# motor_controller_sch.net
KiCad netlist of a schematic drawn in EAGLE
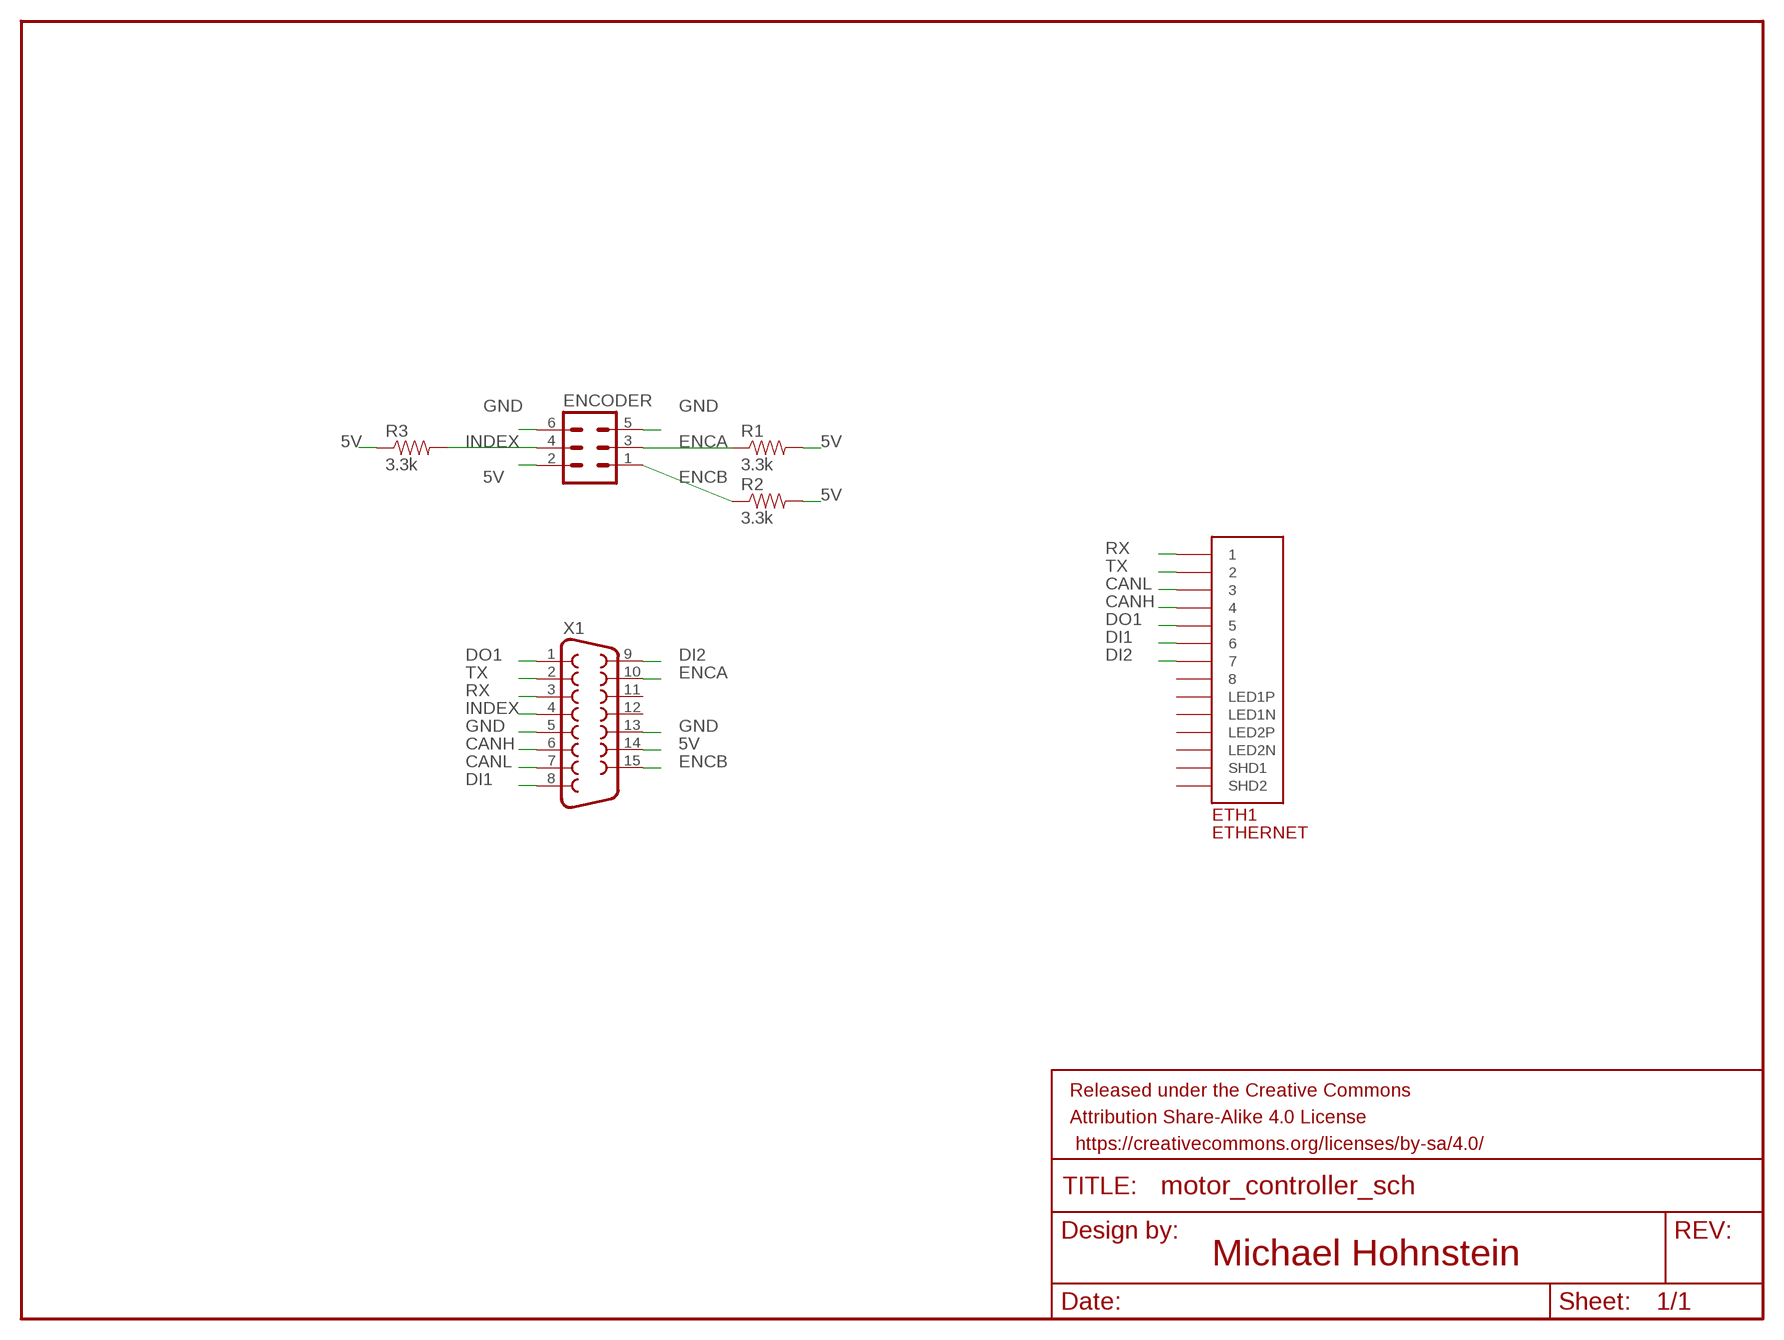
[diagram p0: schematic, sheet 1]

(export (version "E")
  (design (tool "Eeschema 10.0.6"))
  (components
    (comp (ref "ENCODER")
      (value "06V")
      (footprint "eagle-import:06V")
      (libsource (lib "eagle-import") (part "06V"))
    )
    (comp (ref "ETH1")
      (value "ETHERNET")
      (footprint "eagle-import:A122645-ND")
      (libsource (lib "eagle-import") (part "ETHERNET"))
    )
    (comp (ref "FRAME1")
      (value "FRAME-LETTER")
      (footprint "eagle-import:CREATIVE_COMMONS")
      (libsource (lib "eagle-import") (part "FRAME-LETTER"))
    )
    (comp (ref "R1")
      (value "3.3k")
      (footprint "eagle-import:0603-RES")
      (libsource (lib "eagle-import") (part "RESISTOR0603"))
    )
    (comp (ref "R2")
      (value "3.3k")
      (footprint "eagle-import:0603-RES")
      (libsource (lib "eagle-import") (part "RESISTOR0603"))
    )
    (comp (ref "R3")
      (value "3.3k")
      (footprint "eagle-import:0603-RES")
      (libsource (lib "eagle-import") (part "RESISTOR0603"))
    )
    (comp (ref "X1")
      (value "F15HP")
      (footprint "eagle-import:F15HP")
      (libsource (lib "eagle-import") (part "F15HP"))
    )
  )
  (nets
    (net (code "1") (name "/5V") (class "Default")
      (node (ref "ENCODER") (pin "2") (pinfunction "2_2") (pintype "passive"))
      (node (ref "R1") (pin "2") (pinfunction "2_2") (pintype "passive"))
      (node (ref "R2") (pin "2") (pinfunction "2_2") (pintype "passive"))
      (node (ref "R3") (pin "1") (pinfunction "1_1") (pintype "passive"))
      (node (ref "X1") (pin "14") (pinfunction "14_14") (pintype "passive"))
    )
    (net (code "2") (name "/CANH") (class "Default")
      (node (ref "ETH1") (pin "P$4") (pinfunction "4_P$4") (pintype "bidirectional"))
      (node (ref "X1") (pin "6") (pinfunction "6_6") (pintype "passive"))
    )
    (net (code "3") (name "/CANL") (class "Default")
      (node (ref "ETH1") (pin "P$3") (pinfunction "3_P$3") (pintype "bidirectional"))
      (node (ref "X1") (pin "7") (pinfunction "7_7") (pintype "passive"))
    )
    (net (code "4") (name "/DI1") (class "Default")
      (node (ref "ETH1") (pin "P$6") (pinfunction "6_P$6") (pintype "bidirectional"))
      (node (ref "X1") (pin "8") (pinfunction "8_8") (pintype "passive"))
    )
    (net (code "5") (name "/DI2") (class "Default")
      (node (ref "ETH1") (pin "P$7") (pinfunction "7_P$7") (pintype "bidirectional"))
      (node (ref "X1") (pin "9") (pinfunction "9_9") (pintype "passive"))
    )
    (net (code "6") (name "/DO1") (class "Default")
      (node (ref "ETH1") (pin "P$5") (pinfunction "5_P$5") (pintype "bidirectional"))
      (node (ref "X1") (pin "1") (pinfunction "1_1") (pintype "passive"))
    )
    (net (code "7") (name "/ENCA") (class "Default")
      (node (ref "ENCODER") (pin "3") (pinfunction "3_3") (pintype "passive"))
      (node (ref "R1") (pin "1") (pinfunction "1_1") (pintype "passive"))
      (node (ref "X1") (pin "10") (pinfunction "10_10") (pintype "passive"))
    )
    (net (code "8") (name "/ENCB") (class "Default")
      (node (ref "ENCODER") (pin "1") (pinfunction "1_1") (pintype "passive"))
      (node (ref "R2") (pin "1") (pinfunction "1_1") (pintype "passive"))
      (node (ref "X1") (pin "15") (pinfunction "15_15") (pintype "passive"))
    )
    (net (code "9") (name "/GND") (class "Default")
      (node (ref "ENCODER") (pin "5") (pinfunction "5_5") (pintype "passive"))
      (node (ref "ENCODER") (pin "6") (pinfunction "6_6") (pintype "passive"))
      (node (ref "X1") (pin "13") (pinfunction "13_13") (pintype "passive"))
      (node (ref "X1") (pin "5") (pinfunction "5_5") (pintype "passive"))
    )
    (net (code "10") (name "/INDEX") (class "Default")
      (node (ref "ENCODER") (pin "4") (pinfunction "4_4") (pintype "passive"))
      (node (ref "R3") (pin "2") (pinfunction "2_2") (pintype "passive"))
      (node (ref "X1") (pin "4") (pinfunction "4_4") (pintype "passive"))
    )
    (net (code "11") (name "/RX") (class "Default")
      (node (ref "ETH1") (pin "P$1") (pinfunction "1_P$1") (pintype "bidirectional"))
      (node (ref "X1") (pin "3") (pinfunction "3_3") (pintype "passive"))
    )
    (net (code "12") (name "/TX") (class "Default")
      (node (ref "ETH1") (pin "P$2") (pinfunction "2_P$2") (pintype "bidirectional"))
      (node (ref "X1") (pin "2") (pinfunction "2_2") (pintype "passive"))
    )
    (net (code "13") (name "unconnected-(ETH1-8-PadP$8)") (class "Default")
      (node (ref "ETH1") (pin "P$8") (pinfunction "8_P$8") (pintype "bidirectional"))
    )
    (net (code "14") (name "unconnected-(ETH1-LED1N-PadP$9)") (class "Default")
      (node (ref "ETH1") (pin "P$9") (pinfunction "LED1N_P$9") (pintype "bidirectional"))
    )
    (net (code "15") (name "unconnected-(ETH1-LED1P-PadP$10)") (class "Default")
      (node (ref "ETH1") (pin "P$10") (pinfunction "LED1P_P$10") (pintype "bidirectional"))
    )
    (net (code "16") (name "unconnected-(ETH1-LED2N-PadP$11)") (class "Default")
      (node (ref "ETH1") (pin "P$11") (pinfunction "LED2N_P$11") (pintype "bidirectional"))
    )
    (net (code "17") (name "unconnected-(ETH1-LED2P-PadP$12)") (class "Default")
      (node (ref "ETH1") (pin "P$12") (pinfunction "LED2P_P$12") (pintype "bidirectional"))
    )
    (net (code "18") (name "unconnected-(ETH1-SHD1-PadP$13)") (class "Default")
      (node (ref "ETH1") (pin "P$13") (pinfunction "SHD1_P$13") (pintype "bidirectional"))
    )
    (net (code "19") (name "unconnected-(ETH1-SHD2-PadP$14)") (class "Default")
      (node (ref "ETH1") (pin "P$14") (pinfunction "SHD2_P$14") (pintype "bidirectional"))
    )
    (net (code "20") (name "unconnected-(X1-Pad11)") (class "Default")
      (node (ref "X1") (pin "11") (pinfunction "11_11") (pintype "passive"))
    )
    (net (code "21") (name "unconnected-(X1-Pad12)") (class "Default")
      (node (ref "X1") (pin "12") (pinfunction "12_12") (pintype "passive"))
    )
  )
)
